# 2-RJ45.net
KiCad netlist of a schematic drawn in Altium Designer
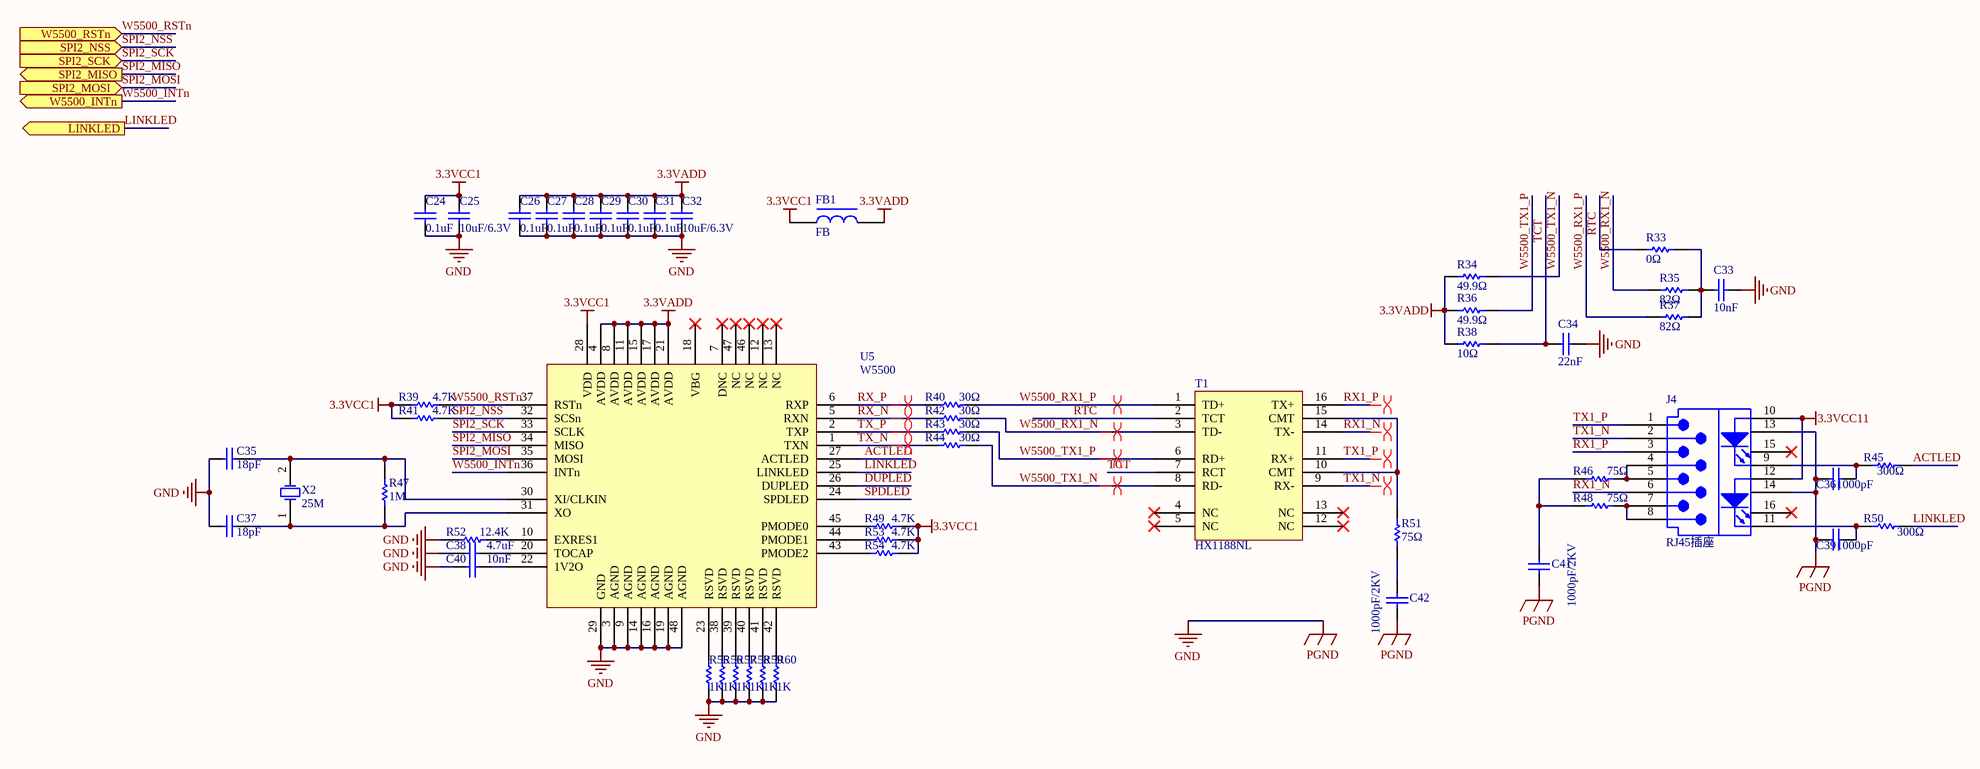
[diagram p0: 2-RJ45.SchDoc]

(export (version "E")
  (design (tool "Eeschema 10.0.6"))
  (components
    (comp (ref "C24")
      (value "0.1uF")
      (footprint "C0603")
      (description "贴片电容_GRM188R71H104KA01D_0.1uF±10%,50V,0603")
      (libsource (lib "20贴片电容0603") (part "0.1uF贴片电容"))
    )
    (comp (ref "C25")
      (value "10uF/6.3V")
      (footprint "C0603")
      (description "贴片电容_GRM188R60J106ME47D_10uF±20%,6.3V,0603")
      (libsource (lib "20贴片电容0603") (part "10uF贴片电容"))
    )
    (comp (ref "C26")
      (value "0.1uF")
      (footprint "C0603")
      (description "贴片电容_GRM188R71H104KA01D_0.1uF±10%,50V,0603")
      (libsource (lib "20贴片电容0603") (part "0.1uF贴片电容"))
    )
    (comp (ref "C27")
      (value "0.1uF")
      (footprint "C0603")
      (description "贴片电容_GRM188R71H104KA01D_0.1uF±10%,50V,0603")
      (libsource (lib "20贴片电容0603") (part "0.1uF贴片电容"))
    )
    (comp (ref "C28")
      (value "0.1uF")
      (footprint "C0603")
      (description "贴片电容_GRM188R71H104KA01D_0.1uF±10%,50V,0603")
      (libsource (lib "20贴片电容0603") (part "0.1uF贴片电容"))
    )
    (comp (ref "C29")
      (value "0.1uF")
      (footprint "C0603")
      (description "贴片电容_GRM188R71H104KA01D_0.1uF±10%,50V,0603")
      (libsource (lib "20贴片电容0603") (part "0.1uF贴片电容"))
    )
    (comp (ref "C30")
      (value "0.1uF")
      (footprint "C0603")
      (description "贴片电容_GRM188R71H104KA01D_0.1uF±10%,50V,0603")
      (libsource (lib "20贴片电容0603") (part "0.1uF贴片电容"))
    )
    (comp (ref "C31")
      (value "0.1uF")
      (footprint "C0603")
      (description "贴片电容_GRM188R71H104KA01D_0.1uF±10%,50V,0603")
      (libsource (lib "20贴片电容0603") (part "0.1uF贴片电容"))
    )
    (comp (ref "C32")
      (value "10uF/6.3V")
      (footprint "C0603")
      (description "贴片电容_GRM188R60J106ME47D_10uF±20%,6.3V,0603")
      (libsource (lib "20贴片电容0603") (part "10uF贴片电容"))
    )
    (comp (ref "C33")
      (value "10nF")
      (footprint "C0603")
      (description "贴片电容_10nF±10%,50V,0603")
      (libsource (lib "20贴片电容0603") (part "0.1uF贴片电容"))
    )
    (comp (ref "C34")
      (value "22nF")
      (footprint "C0603")
      (description "贴片电容_22nF±5%,50V,0603")
      (libsource (lib "20贴片电容0603") (part "27nF贴片电容"))
    )
    (comp (ref "C35")
      (value "18pF")
      (footprint "C0603")
      (description "贴片电容_18pF±5%,50V,0603")
      (libsource (lib "20贴片电容0603") (part "20pF贴片电容"))
    )
    (comp (ref "C36")
      (value "1000pF")
      (footprint "C0603")
      (description "贴片电容_GRM188R71H102KA01_1000pF±10%,50V,0603")
      (libsource (lib "20贴片电容0603") (part "1000pF贴片电容"))
    )
    (comp (ref "C37")
      (value "18pF")
      (footprint "C0603")
      (description "贴片电容_18pF±5%,50V,0603")
      (libsource (lib "20贴片电容0603") (part "20pF贴片电容"))
    )
    (comp (ref "C38")
      (value "4.7uF")
      (footprint "C0603")
      (description "贴片电容_4.7uF±10%,50V,0603")
      (libsource (lib "20贴片电容0603") (part "1uF贴片电容"))
    )
    (comp (ref "C39")
      (value "1000pF")
      (footprint "C0603")
      (description "贴片电容_GRM188R71H102KA01_1000pF±10%,50V,0603")
      (libsource (lib "20贴片电容0603") (part "1000pF贴片电容"))
    )
    (comp (ref "C40")
      (value "10nF")
      (footprint "C0603")
      (description "贴片电容_10nF±10%,50V,0603")
      (libsource (lib "20贴片电容0603") (part "0.1uF贴片电容"))
    )
    (comp (ref "C41")
      (value "1000pF/2KV")
      (footprint "C1206")
      (description "贴片电容_1000pF/2KV")
      (libsource (lib "22贴片电容1210") (part "10uF贴片电容"))
    )
    (comp (ref "C42")
      (value "1000pF/2KV")
      (footprint "C1206")
      (description "贴片电容_1000pF/2KV")
      (libsource (lib "22贴片电容1210") (part "10uF贴片电容"))
    )
    (comp (ref "FB1")
      (value "FB")
      (footprint "L0805")
      (description "贴片磁珠_600R,0805")
      (libsource (lib "32贴片磁珠0805") (part "0805贴片磁珠"))
    )
    (comp (ref "J4")
      (value "RJ45插座")
      (footprint "RJ45TH-1x1-2R54-LED")
      (description "RJ45插座_1*1,带左黄右绿灯,弯脚")
      (fields (field (name "MPN") "朱迅"))
      (libsource (lib "91连接器") (part "RJ45弯脚带灯"))
    )
    (comp (ref "R33")
      (value "0Ω")
      (footprint "R0603")
      (description "贴片电阻_0Ω±5%,0603")
      (libsource (lib "10贴片电阻0603") (part "0Ω贴片电阻"))
    )
    (comp (ref "R34")
      (value "49.9Ω")
      (footprint "R0603")
      (description "贴片电阻_49.9Ω±1%,0603")
      (libsource (lib "10贴片电阻0603") (part "51Ω贴片电阻"))
    )
    (comp (ref "R35")
      (value "82Ω")
      (footprint "R0603")
      (description "贴片电阻_82Ω±1%,0603")
      (libsource (lib "10贴片电阻0603") (part "51Ω贴片电阻"))
    )
    (comp (ref "R36")
      (value "49.9Ω")
      (footprint "R0603")
      (description "贴片电阻_49.9Ω±1%,0603")
      (libsource (lib "10贴片电阻0603") (part "51Ω贴片电阻"))
    )
    (comp (ref "R37")
      (value "82Ω")
      (footprint "R0603")
      (description "贴片电阻_82Ω±1%,0603")
      (libsource (lib "10贴片电阻0603") (part "51Ω贴片电阻"))
    )
    (comp (ref "R38")
      (value "10Ω")
      (footprint "R0603")
      (description "贴片电阻_10Ω±5%,0603")
      (libsource (lib "10贴片电阻0603") (part "10Ω贴片电阻"))
    )
    (comp (ref "R39")
      (value "4.7K")
      (footprint "R0603")
      (description "贴片电阻_4.7K±5%,0603")
      (libsource (lib "10贴片电阻0603") (part "4.7K贴片电阻"))
    )
    (comp (ref "R40")
      (value "30Ω")
      (footprint "R0603")
      (description "贴片电阻_30Ω±5%,0603")
      (libsource (lib "10贴片电阻0603") (part "30Ω贴片电阻"))
    )
    (comp (ref "R41")
      (value "4.7K")
      (footprint "R0603")
      (description "贴片电阻_4.7K±5%,0603")
      (libsource (lib "10贴片电阻0603") (part "4.7K贴片电阻"))
    )
    (comp (ref "R42")
      (value "30Ω")
      (footprint "R0603")
      (description "贴片电阻_30Ω±5%,0603")
      (libsource (lib "10贴片电阻0603") (part "30Ω贴片电阻"))
    )
    (comp (ref "R43")
      (value "30Ω")
      (footprint "R0603")
      (description "贴片电阻_30Ω±5%,0603")
      (libsource (lib "10贴片电阻0603") (part "30Ω贴片电阻"))
    )
    (comp (ref "R44")
      (value "30Ω")
      (footprint "R0603")
      (description "贴片电阻_30Ω±5%,0603")
      (libsource (lib "10贴片电阻0603") (part "30Ω贴片电阻"))
    )
    (comp (ref "R45")
      (value "300Ω")
      (footprint "R0603")
      (description "贴片电阻_300Ω±5%,0603")
      (libsource (lib "10贴片电阻0603") (part "300Ω贴片电阻"))
    )
    (comp (ref "R46")
      (value "75Ω")
      (footprint "R0805")
      (description "贴片电阻_75Ω±5%,0805")
      (libsource (lib "11贴片电阻0805") (part "75Ω贴片电阻"))
    )
    (comp (ref "R47")
      (value "1M")
      (footprint "R0603")
      (description "贴片电阻_1M±5%,0603")
      (libsource (lib "10贴片电阻0603") (part "1M贴片电阻"))
    )
    (comp (ref "R48")
      (value "75Ω")
      (footprint "R0805")
      (description "贴片电阻_75Ω±5%,0805")
      (libsource (lib "11贴片电阻0805") (part "75Ω贴片电阻"))
    )
    (comp (ref "R49")
      (value "4.7K")
      (footprint "R0603")
      (description "贴片电阻_4.7K±5%,0603")
      (libsource (lib "10贴片电阻0603") (part "4.7K贴片电阻"))
    )
    (comp (ref "R50")
      (value "300Ω")
      (footprint "R0603")
      (description "贴片电阻_300Ω±5%,0603")
      (libsource (lib "10贴片电阻0603") (part "300Ω贴片电阻"))
    )
    (comp (ref "R51")
      (value "75Ω")
      (footprint "R1206")
      (description "贴片电阻_75Ω±5%,1206")
      (libsource (lib "11贴片电阻0805") (part "75Ω贴片电阻"))
    )
    (comp (ref "R52")
      (value "12.4K")
      (footprint "R0603")
      (description "贴片电阻_12.4K±1%,0603")
      (libsource (lib "10贴片电阻0603") (part "12K贴片电阻"))
    )
    (comp (ref "R53")
      (value "4.7K")
      (footprint "R0603")
      (description "贴片电阻_4.7K±5%,0603")
      (libsource (lib "10贴片电阻0603") (part "4.7K贴片电阻"))
    )
    (comp (ref "R54")
      (value "4.7K")
      (footprint "R0603")
      (description "贴片电阻_4.7K±5%,0603")
      (libsource (lib "10贴片电阻0603") (part "4.7K贴片电阻"))
    )
    (comp (ref "R55")
      (value "1K")
      (footprint "R0603")
      (description "贴片电阻_1K±5%,0603")
      (libsource (lib "10贴片电阻0603") (part "1K贴片电阻"))
    )
    (comp (ref "R56")
      (value "1K")
      (footprint "R0603")
      (description "贴片电阻_1K±5%,0603")
      (libsource (lib "10贴片电阻0603") (part "1K贴片电阻"))
    )
    (comp (ref "R57")
      (value "1K")
      (footprint "R0603")
      (description "贴片电阻_1K±5%,0603")
      (libsource (lib "10贴片电阻0603") (part "1K贴片电阻"))
    )
    (comp (ref "R58")
      (value "1K")
      (footprint "R0603")
      (description "贴片电阻_1K±5%,0603")
      (libsource (lib "10贴片电阻0603") (part "1K贴片电阻"))
    )
    (comp (ref "R59")
      (value "1K")
      (footprint "R0603")
      (description "贴片电阻_1K±5%,0603")
      (libsource (lib "10贴片电阻0603") (part "1K贴片电阻"))
    )
    (comp (ref "R60")
      (value "1K")
      (footprint "R0603")
      (description "贴片电阻_1K±5%,0603")
      (libsource (lib "10贴片电阻0603") (part "1K贴片电阻"))
    )
    (comp (ref "T1")
      (value "HX1188NL")
      (footprint "SOP16-1R27-7R11x12R7")
      (description "网络变压器_HX1188NL_百兆,SOIC16")
      (libsource (lib "89网络变压器") (part "HX1188NL"))
    )
    (comp (ref "U5")
      (value "W5500")
      (footprint "TQFN48-0R5-7X7")
      (description "以太网控制器_W5500_LQFP48")
      (libsource (lib "86网口芯片") (part "W5500"))
    )
    (comp (ref "X2")
      (value "25M")
      (footprint "CRY2SM-6R0x3R5")
      (description "贴片无源晶体_25MHz,30ppm,6035封装")
      (libsource (lib "60振荡器") (part "25M贴片无源晶体"))
    )
  )
  (nets
    (net (code "1") (name "/ACTLED") (class "Default")
      (node (ref "R45") (pin "2") (pinfunction "2_2") (pintype "passive"))
      (node (ref "U5") (pin "27") (pinfunction "ACTLED_27") (pintype "passive"))
    )
    (net (code "2") (name "/DUPLED") (class "Default")
      (node (ref "U5") (pin "26") (pinfunction "DUPLED_26") (pintype "passive"))
    )
    (net (code "3") (name "/LINKLED") (class "Default")
      (node (ref "R50") (pin "2") (pinfunction "2_2") (pintype "passive"))
      (node (ref "U5") (pin "25") (pinfunction "LINKLED_25") (pintype "passive"))
    )
    (net (code "4") (name "/RTC") (class "Default")
      (node (ref "R33") (pin "2") (pinfunction "2_2") (pintype "passive"))
      (node (ref "T1") (pin "2") (pinfunction "TCT_2") (pintype "passive"))
    )
    (net (code "5") (name "/RX1_N") (class "Default")
      (node (ref "J4") (pin "6") (pinfunction "RX-_6") (pintype "passive"))
      (node (ref "T1") (pin "14") (pinfunction "TX-_14") (pintype "passive"))
    )
    (net (code "6") (name "/RX1_P") (class "Default")
      (node (ref "J4") (pin "3") (pinfunction "RX+_3") (pintype "passive"))
      (node (ref "T1") (pin "16") (pinfunction "TX+_16") (pintype "passive"))
    )
    (net (code "7") (name "/RX_N") (class "Default")
      (node (ref "R42") (pin "1") (pinfunction "1_1") (pintype "passive"))
      (node (ref "U5") (pin "5") (pinfunction "RXN_5") (pintype "passive"))
    )
    (net (code "8") (name "/RX_P") (class "Default")
      (node (ref "R40") (pin "1") (pinfunction "1_1") (pintype "passive"))
      (node (ref "U5") (pin "6") (pinfunction "RXP_6") (pintype "passive"))
    )
    (net (code "9") (name "/SPDLED") (class "Default")
      (node (ref "U5") (pin "24") (pinfunction "SPDLED_24") (pintype "passive"))
    )
    (net (code "10") (name "/SPI2_MISO") (class "Default")
      (node (ref "U5") (pin "34") (pinfunction "MISO_34") (pintype "passive"))
    )
    (net (code "11") (name "/SPI2_MOSI") (class "Default")
      (node (ref "U5") (pin "35") (pinfunction "MOSI_35") (pintype "passive"))
    )
    (net (code "12") (name "/SPI2_NSS") (class "Default")
      (node (ref "R41") (pin "1") (pinfunction "1_1") (pintype "passive"))
      (node (ref "U5") (pin "32") (pinfunction "SCSn_32") (pintype "passive"))
    )
    (net (code "13") (name "/SPI2_SCK") (class "Default")
      (node (ref "U5") (pin "33") (pinfunction "SCLK_33") (pintype "passive"))
    )
    (net (code "14") (name "/TCT") (class "Default")
      (node (ref "C34") (pin "2") (pinfunction "2_2") (pintype "passive"))
      (node (ref "R38") (pin "1") (pinfunction "1_1") (pintype "passive"))
      (node (ref "T1") (pin "7") (pinfunction "RCT_7") (pintype "passive"))
    )
    (net (code "15") (name "/TX1_N") (class "Default")
      (node (ref "J4") (pin "2") (pinfunction "TX-_2") (pintype "passive"))
      (node (ref "T1") (pin "9") (pinfunction "RX-_9") (pintype "passive"))
    )
    (net (code "16") (name "/TX1_P") (class "Default")
      (node (ref "J4") (pin "1") (pinfunction "TX+_1") (pintype "passive"))
      (node (ref "T1") (pin "11") (pinfunction "RX+_11") (pintype "passive"))
    )
    (net (code "17") (name "/TX_N") (class "Default")
      (node (ref "R44") (pin "1") (pinfunction "1_1") (pintype "passive"))
      (node (ref "U5") (pin "1") (pinfunction "TXN_1") (pintype "passive"))
    )
    (net (code "18") (name "/TX_P") (class "Default")
      (node (ref "R43") (pin "1") (pinfunction "1_1") (pintype "passive"))
      (node (ref "U5") (pin "2") (pinfunction "TXP_2") (pintype "passive"))
    )
    (net (code "19") (name "/W5500_INTn") (class "Default")
      (node (ref "U5") (pin "36") (pinfunction "INTn_36") (pintype "passive"))
    )
    (net (code "20") (name "/W5500_RSTn") (class "Default")
      (node (ref "R39") (pin "1") (pinfunction "1_1") (pintype "passive"))
      (node (ref "U5") (pin "37") (pinfunction "RSTn_37") (pintype "passive"))
    )
    (net (code "21") (name "/W5500_RX1_N") (class "Default")
      (node (ref "R35") (pin "2") (pinfunction "2_2") (pintype "passive"))
      (node (ref "R42") (pin "2") (pinfunction "2_2") (pintype "passive"))
      (node (ref "T1") (pin "3") (pinfunction "TD-_3") (pintype "passive"))
    )
    (net (code "22") (name "/W5500_RX1_P") (class "Default")
      (node (ref "R37") (pin "2") (pinfunction "2_2") (pintype "passive"))
      (node (ref "R40") (pin "2") (pinfunction "2_2") (pintype "passive"))
      (node (ref "T1") (pin "1") (pinfunction "TD+_1") (pintype "passive"))
    )
    (net (code "23") (name "/W5500_TX1_N") (class "Default")
      (node (ref "R34") (pin "1") (pinfunction "1_1") (pintype "passive"))
      (node (ref "R44") (pin "2") (pinfunction "2_2") (pintype "passive"))
      (node (ref "T1") (pin "8") (pinfunction "RD-_8") (pintype "passive"))
    )
    (net (code "24") (name "/W5500_TX1_P") (class "Default")
      (node (ref "R36") (pin "1") (pinfunction "1_1") (pintype "passive"))
      (node (ref "R43") (pin "2") (pinfunction "2_2") (pintype "passive"))
      (node (ref "T1") (pin "6") (pinfunction "RD+_6") (pintype "passive"))
    )
    (net (code "25") (name "3.3VADD") (class "Default")
      (node (ref "C26") (pin "2") (pinfunction "2_2") (pintype "passive"))
      (node (ref "C27") (pin "2") (pinfunction "2_2") (pintype "passive"))
      (node (ref "C28") (pin "2") (pinfunction "2_2") (pintype "passive"))
      (node (ref "C29") (pin "2") (pinfunction "2_2") (pintype "passive"))
      (node (ref "C30") (pin "2") (pinfunction "2_2") (pintype "passive"))
      (node (ref "C31") (pin "2") (pinfunction "2_2") (pintype "passive"))
      (node (ref "C32") (pin "2") (pinfunction "2_2") (pintype "passive"))
      (node (ref "FB1") (pin "2") (pinfunction "2_2") (pintype "passive"))
      (node (ref "R34") (pin "2") (pinfunction "2_2") (pintype "passive"))
      (node (ref "R36") (pin "2") (pinfunction "2_2") (pintype "passive"))
      (node (ref "R38") (pin "2") (pinfunction "2_2") (pintype "passive"))
      (node (ref "U5") (pin "11") (pinfunction "AVDD_11") (pintype "passive"))
      (node (ref "U5") (pin "15") (pinfunction "AVDD_15") (pintype "passive"))
      (node (ref "U5") (pin "17") (pinfunction "AVDD_17") (pintype "passive"))
      (node (ref "U5") (pin "21") (pinfunction "AVDD_21") (pintype "passive"))
      (node (ref "U5") (pin "4") (pinfunction "AVDD_4") (pintype "passive"))
      (node (ref "U5") (pin "8") (pinfunction "AVDD_8") (pintype "passive"))
    )
    (net (code "26") (name "3.3VCC1") (class "Default")
      (node (ref "C24") (pin "2") (pinfunction "2_2") (pintype "passive"))
      (node (ref "C25") (pin "2") (pinfunction "2_2") (pintype "passive"))
      (node (ref "FB1") (pin "1") (pinfunction "1_1") (pintype "passive"))
      (node (ref "R39") (pin "2") (pinfunction "2_2") (pintype "passive"))
      (node (ref "R41") (pin "2") (pinfunction "2_2") (pintype "passive"))
      (node (ref "R49") (pin "2") (pinfunction "2_2") (pintype "passive"))
      (node (ref "R53") (pin "2") (pinfunction "2_2") (pintype "passive"))
      (node (ref "R54") (pin "2") (pinfunction "2_2") (pintype "passive"))
      (node (ref "U5") (pin "28") (pinfunction "VDD_28") (pintype "passive"))
    )
    (net (code "27") (name "3.3VCC11") (class "Default")
      (node (ref "J4") (pin "10") (pinfunction "A1_10") (pintype "passive"))
      (node (ref "J4") (pin "12") (pinfunction "A2_12") (pintype "passive"))
    )
    (net (code "28") (name "GND") (class "Default")
      (node (ref "C24") (pin "1") (pinfunction "1_1") (pintype "passive"))
      (node (ref "C25") (pin "1") (pinfunction "1_1") (pintype "passive"))
      (node (ref "C26") (pin "1") (pinfunction "1_1") (pintype "passive"))
      (node (ref "C27") (pin "1") (pinfunction "1_1") (pintype "passive"))
      (node (ref "C28") (pin "1") (pinfunction "1_1") (pintype "passive"))
      (node (ref "C29") (pin "1") (pinfunction "1_1") (pintype "passive"))
      (node (ref "C30") (pin "1") (pinfunction "1_1") (pintype "passive"))
      (node (ref "C31") (pin "1") (pinfunction "1_1") (pintype "passive"))
      (node (ref "C32") (pin "1") (pinfunction "1_1") (pintype "passive"))
      (node (ref "C33") (pin "1") (pinfunction "1_1") (pintype "passive"))
      (node (ref "C34") (pin "1") (pinfunction "1_1") (pintype "passive"))
      (node (ref "C35") (pin "1") (pinfunction "1_1") (pintype "passive"))
      (node (ref "C36") (pin "1") (pinfunction "1_1") (pintype "passive"))
      (node (ref "C37") (pin "1") (pinfunction "1_1") (pintype "passive"))
      (node (ref "C38") (pin "1") (pinfunction "1_1") (pintype "passive"))
      (node (ref "C39") (pin "1") (pinfunction "1_1") (pintype "passive"))
      (node (ref "C40") (pin "1") (pinfunction "1_1") (pintype "passive"))
      (node (ref "C41") (pin "1") (pinfunction "1_1") (pintype "passive"))
      (node (ref "C42") (pin "1") (pinfunction "1_1") (pintype "passive"))
      (node (ref "J4") (pin "13") (pinfunction "13_13") (pintype "passive"))
      (node (ref "J4") (pin "14") (pinfunction "14_14") (pintype "passive"))
      (node (ref "R52") (pin "1") (pinfunction "1_1") (pintype "passive"))
      (node (ref "R55") (pin "1") (pinfunction "1_1") (pintype "passive"))
      (node (ref "R56") (pin "1") (pinfunction "1_1") (pintype "passive"))
      (node (ref "R57") (pin "1") (pinfunction "1_1") (pintype "passive"))
      (node (ref "R58") (pin "1") (pinfunction "1_1") (pintype "passive"))
      (node (ref "R59") (pin "1") (pinfunction "1_1") (pintype "passive"))
      (node (ref "R60") (pin "1") (pinfunction "1_1") (pintype "passive"))
      (node (ref "U5") (pin "14") (pinfunction "AGND_14") (pintype "passive"))
      (node (ref "U5") (pin "16") (pinfunction "AGND_16") (pintype "passive"))
      (node (ref "U5") (pin "19") (pinfunction "AGND_19") (pintype "passive"))
      (node (ref "U5") (pin "29") (pinfunction "GND_29") (pintype "passive"))
      (node (ref "U5") (pin "3") (pinfunction "AGND_3") (pintype "passive"))
      (node (ref "U5") (pin "48") (pinfunction "AGND_48") (pintype "passive"))
      (node (ref "U5") (pin "9") (pinfunction "AGND_9") (pintype "passive"))
    )
    (net (code "29") (name "Net-(C33-Pad2)") (class "Default")
      (node (ref "C33") (pin "2") (pinfunction "2_2") (pintype "passive"))
      (node (ref "R33") (pin "1") (pinfunction "1_1") (pintype "passive"))
      (node (ref "R35") (pin "1") (pinfunction "1_1") (pintype "passive"))
      (node (ref "R37") (pin "1") (pinfunction "1_1") (pintype "passive"))
    )
    (net (code "30") (name "Net-(C41-Pad2)") (class "Default")
      (node (ref "C41") (pin "2") (pinfunction "2_2") (pintype "passive"))
      (node (ref "R46") (pin "1") (pinfunction "1_1") (pintype "passive"))
      (node (ref "R48") (pin "1") (pinfunction "1_1") (pintype "passive"))
    )
    (net (code "31") (name "Net-(C42-Pad2)") (class "Default")
      (node (ref "C42") (pin "2") (pinfunction "2_2") (pintype "passive"))
      (node (ref "R51") (pin "1") (pinfunction "1_1") (pintype "passive"))
    )
    (net (code "32") (name "Net-(J4-K1)") (class "Default")
      (node (ref "C36") (pin "2") (pinfunction "2_2") (pintype "passive"))
      (node (ref "J4") (pin "9") (pinfunction "K1_9") (pintype "passive"))
      (node (ref "R45") (pin "1") (pinfunction "1_1") (pintype "passive"))
    )
    (net (code "33") (name "Net-(J4-K2)") (class "Default")
      (node (ref "C39") (pin "2") (pinfunction "2_2") (pintype "passive"))
      (node (ref "J4") (pin "11") (pinfunction "K2_11") (pintype "passive"))
      (node (ref "R50") (pin "1") (pinfunction "1_1") (pintype "passive"))
    )
    (net (code "34") (name "Net-(J4-NC-Pad4)") (class "Default")
      (node (ref "J4") (pin "4") (pinfunction "NC_4") (pintype "passive"))
      (node (ref "J4") (pin "5") (pinfunction "NC_5") (pintype "passive"))
      (node (ref "R46") (pin "2") (pinfunction "2_2") (pintype "passive"))
    )
    (net (code "35") (name "Net-(J4-NC-Pad7)") (class "Default")
      (node (ref "J4") (pin "7") (pinfunction "NC_7") (pintype "passive"))
      (node (ref "J4") (pin "8") (pinfunction "NC_8") (pintype "passive"))
      (node (ref "R48") (pin "2") (pinfunction "2_2") (pintype "passive"))
    )
    (net (code "36") (name "Net-(R51-Pad2)") (class "Default")
      (node (ref "R51") (pin "2") (pinfunction "2_2") (pintype "passive"))
      (node (ref "T1") (pin "10") (pinfunction "CMT_10") (pintype "passive"))
      (node (ref "T1") (pin "15") (pinfunction "CMT_15") (pintype "passive"))
    )
    (net (code "37") (name "Net-(R55-Pad2)") (class "Default")
      (node (ref "R55") (pin "2") (pinfunction "2_2") (pintype "passive"))
      (node (ref "U5") (pin "23") (pinfunction "RSVD_23") (pintype "passive"))
    )
    (net (code "38") (name "Net-(R56-Pad2)") (class "Default")
      (node (ref "R56") (pin "2") (pinfunction "2_2") (pintype "passive"))
      (node (ref "U5") (pin "38") (pinfunction "RSVD_38") (pintype "passive"))
    )
    (net (code "39") (name "Net-(R57-Pad2)") (class "Default")
      (node (ref "R57") (pin "2") (pinfunction "2_2") (pintype "passive"))
      (node (ref "U5") (pin "39") (pinfunction "RSVD_39") (pintype "passive"))
    )
    (net (code "40") (name "Net-(R58-Pad2)") (class "Default")
      (node (ref "R58") (pin "2") (pinfunction "2_2") (pintype "passive"))
      (node (ref "U5") (pin "40") (pinfunction "RSVD_40") (pintype "passive"))
    )
    (net (code "41") (name "Net-(R59-Pad2)") (class "Default")
      (node (ref "R59") (pin "2") (pinfunction "2_2") (pintype "passive"))
      (node (ref "U5") (pin "41") (pinfunction "RSVD_41") (pintype "passive"))
    )
    (net (code "42") (name "Net-(R60-Pad2)") (class "Default")
      (node (ref "R60") (pin "2") (pinfunction "2_2") (pintype "passive"))
      (node (ref "U5") (pin "42") (pinfunction "RSVD_42") (pintype "passive"))
    )
    (net (code "43") (name "Net-(U5-1V2O)") (class "Default")
      (node (ref "C40") (pin "2") (pinfunction "2_2") (pintype "passive"))
      (node (ref "U5") (pin "22") (pinfunction "1V2O_22") (pintype "passive"))
    )
    (net (code "44") (name "Net-(U5-EXRES1)") (class "Default")
      (node (ref "R52") (pin "2") (pinfunction "2_2") (pintype "passive"))
      (node (ref "U5") (pin "10") (pinfunction "EXRES1_10") (pintype "passive"))
    )
    (net (code "45") (name "Net-(U5-PMODE0)") (class "Default")
      (node (ref "R49") (pin "1") (pinfunction "1_1") (pintype "passive"))
      (node (ref "U5") (pin "45") (pinfunction "PMODE0_45") (pintype "passive"))
    )
    (net (code "46") (name "Net-(U5-PMODE1)") (class "Default")
      (node (ref "R53") (pin "1") (pinfunction "1_1") (pintype "passive"))
      (node (ref "U5") (pin "44") (pinfunction "PMODE1_44") (pintype "passive"))
    )
    (net (code "47") (name "Net-(U5-PMODE2)") (class "Default")
      (node (ref "R54") (pin "1") (pinfunction "1_1") (pintype "passive"))
      (node (ref "U5") (pin "43") (pinfunction "PMODE2_43") (pintype "passive"))
    )
    (net (code "48") (name "Net-(U5-TOCAP)") (class "Default")
      (node (ref "C38") (pin "2") (pinfunction "2_2") (pintype "passive"))
      (node (ref "U5") (pin "20") (pinfunction "TOCAP_20") (pintype "passive"))
    )
    (net (code "49") (name "Net-(U5-XI{slash}CLKIN)") (class "Default")
      (node (ref "C35") (pin "2") (pinfunction "2_2") (pintype "passive"))
      (node (ref "R47") (pin "2") (pinfunction "2_2") (pintype "passive"))
      (node (ref "U5") (pin "30") (pinfunction "XI/CLKIN_30") (pintype "passive"))
      (node (ref "X2") (pin "2") (pinfunction "OSC2_2") (pintype "passive"))
    )
    (net (code "50") (name "Net-(U5-XO)") (class "Default")
      (node (ref "C37") (pin "2") (pinfunction "2_2") (pintype "passive"))
      (node (ref "R47") (pin "1") (pinfunction "1_1") (pintype "passive"))
      (node (ref "U5") (pin "31") (pinfunction "XO_31") (pintype "passive"))
      (node (ref "X2") (pin "1") (pinfunction "OSC1_1") (pintype "passive"))
    )
    (net (code "51") (name "unconnected-(J4-Pad15)") (class "Default")
      (node (ref "J4") (pin "15") (pinfunction "15_15") (pintype "passive+no_connect"))
    )
    (net (code "52") (name "unconnected-(J4-Pad16)") (class "Default")
      (node (ref "J4") (pin "16") (pinfunction "16_16") (pintype "passive+no_connect"))
    )
    (net (code "53") (name "unconnected-(T1-NC-Pad4)") (class "Default")
      (node (ref "T1") (pin "4") (pinfunction "NC_4") (pintype "passive+no_connect"))
    )
    (net (code "54") (name "unconnected-(T1-NC-Pad5)") (class "Default")
      (node (ref "T1") (pin "5") (pinfunction "NC_5") (pintype "passive+no_connect"))
    )
    (net (code "55") (name "unconnected-(T1-NC-Pad12)") (class "Default")
      (node (ref "T1") (pin "12") (pinfunction "NC_12") (pintype "passive+no_connect"))
    )
    (net (code "56") (name "unconnected-(T1-NC-Pad13)") (class "Default")
      (node (ref "T1") (pin "13") (pinfunction "NC_13") (pintype "passive+no_connect"))
    )
    (net (code "57") (name "unconnected-(U5-DNC-Pad7)") (class "Default")
      (node (ref "U5") (pin "7") (pinfunction "DNC_7") (pintype "passive+no_connect"))
    )
    (net (code "58") (name "unconnected-(U5-NC-Pad12)") (class "Default")
      (node (ref "U5") (pin "12") (pinfunction "NC_12") (pintype "passive+no_connect"))
    )
    (net (code "59") (name "unconnected-(U5-NC-Pad13)") (class "Default")
      (node (ref "U5") (pin "13") (pinfunction "NC_13") (pintype "passive+no_connect"))
    )
    (net (code "60") (name "unconnected-(U5-NC-Pad46)") (class "Default")
      (node (ref "U5") (pin "46") (pinfunction "NC_46") (pintype "passive+no_connect"))
    )
    (net (code "61") (name "unconnected-(U5-NC-Pad47)") (class "Default")
      (node (ref "U5") (pin "47") (pinfunction "NC_47") (pintype "passive+no_connect"))
    )
    (net (code "62") (name "unconnected-(U5-VBG-Pad18)") (class "Default")
      (node (ref "U5") (pin "18") (pinfunction "VBG_18") (pintype "passive+no_connect"))
    )
  )
)
